# Mandala.net
KiCad netlist of a schematic drawn in EAGLE
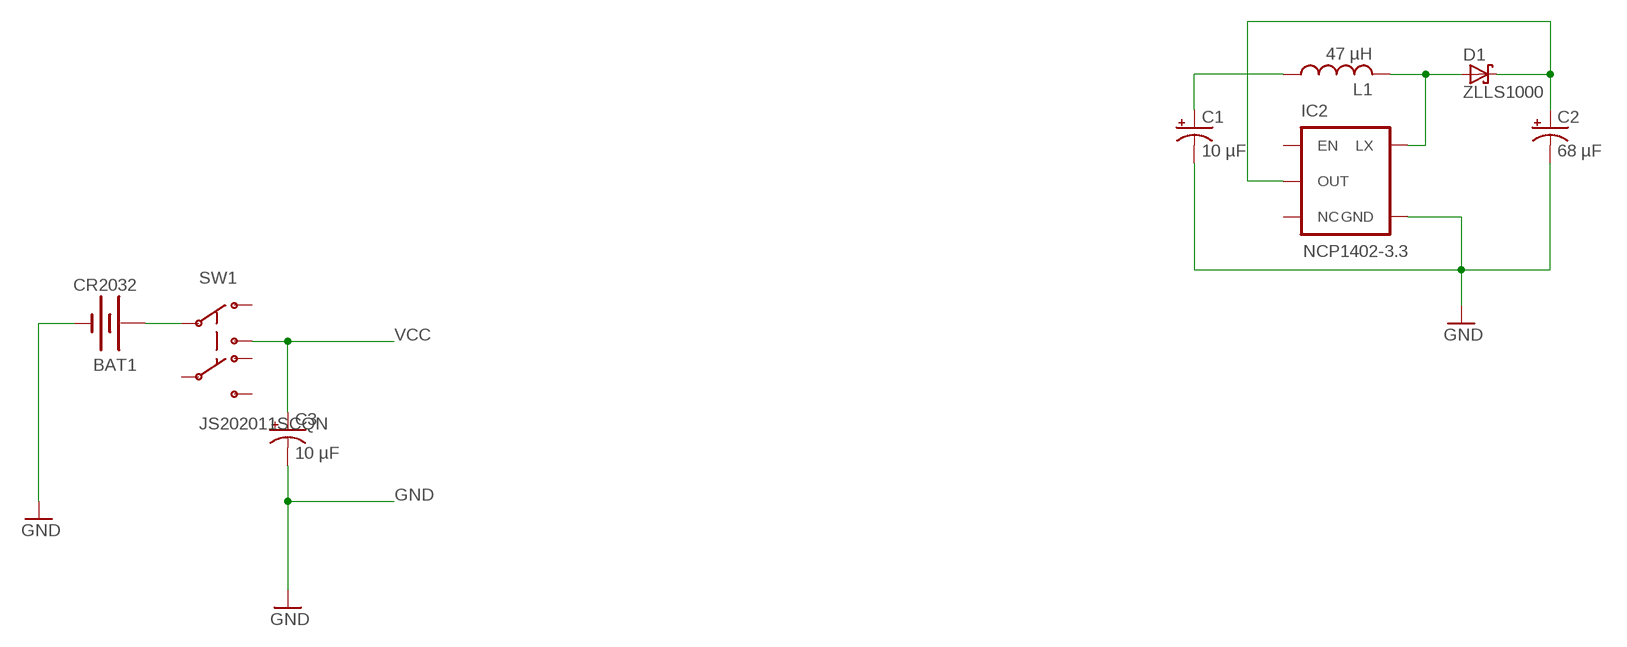
[diagram p0: schematic, sheet 1]

(export (version "E")
  (design (tool "Eeschema 10.0.6"))
  (components
    (comp (ref "BAT1")
      (value "CR2032")
      (footprint "eagle-import:BATTCON_20MM")
      (libsource (lib "eagle-import") (part "BATTERY20SMD-RIGHT"))
    )
    (comp (ref "C1")
      (value "10 µF")
      (footprint "eagle-import:SMC_B")
      (libsource (lib "eagle-import") (part "CPOL-USSMCB"))
    )
    (comp (ref "C2")
      (value "68 µF")
      (footprint "eagle-import:SMC_B")
      (libsource (lib "eagle-import") (part "CPOL-USSMCB"))
    )
    (comp (ref "C3")
      (value "10 µF")
      (footprint "eagle-import:SMC_B")
      (libsource (lib "eagle-import") (part "CPOL-USSMCB"))
    )
    (comp (ref "D1")
      (value "ZLLS1000")
      (footprint "eagle-import:SOT23")
      (libsource (lib "eagle-import") (part "BAS40"))
    )
    (comp (ref "IC2")
      (value "NCP1402-3.3")
      (footprint "eagle-import:SOT23-5")
      (libsource (lib "eagle-import") (part "V_REG_NCP1400SOT23-5"))
    )
    (comp (ref "L1")
      (value "47 µH")
      (footprint "eagle-import:ELL5PS_INDUCTOR")
      (libsource (lib "eagle-import") (part "PANASONIC_ELL5PS"))
    )
    (comp (ref "SW1")
      (value "JS202011SCQN")
      (footprint "eagle-import:JS202011SCQN_DPDT")
      (libsource (lib "eagle-import") (part "SW_DPDT_JS202011SCQN"))
    )
  )
  (nets
    (net (code "1") (name "/VCC") (class "Default")
      (node (ref "C1") (pin "+") (pinfunction "+_+") (pintype "passive"))
      (node (ref "C3") (pin "+") (pinfunction "+_+") (pintype "passive"))
      (node (ref "L1") (pin "P$1") (pinfunction "1_P$1") (pintype "passive"))
      (node (ref "SW1") (pin "P$3") (pinfunction "3_P$3") (pintype "bidirectional"))
    )
    (net (code "2") (name "GND") (class "Default")
      (node (ref "BAT1") (pin "2") (pinfunction "-_2") (pintype "power_in"))
      (node (ref "C1") (pin "-") (pinfunction "-_-") (pintype "passive"))
      (node (ref "C2") (pin "-") (pinfunction "-_-") (pintype "passive"))
      (node (ref "C3") (pin "-") (pinfunction "-_-") (pintype "passive"))
      (node (ref "IC2") (pin "4") (pinfunction "GND_4") (pintype "input"))
    )
    (net (code "3") (name "Net-(BAT1-+)") (class "Default")
      (node (ref "BAT1") (pin "3") (pinfunction "+_3") (pintype "power_in"))
      (node (ref "SW1") (pin "P$2") (pinfunction "2_P$2") (pintype "bidirectional"))
    )
    (net (code "4") (name "Net-(D1-A)") (class "Default")
      (node (ref "D1") (pin "1") (pinfunction "A_1") (pintype "passive"))
      (node (ref "IC2") (pin "5") (pinfunction "LX_5") (pintype "input"))
      (node (ref "L1") (pin "P$2") (pinfunction "2_P$2") (pintype "passive"))
    )
    (net (code "5") (name "Net-(D1-C)") (class "Default")
      (node (ref "C2") (pin "+") (pinfunction "+_+") (pintype "passive"))
      (node (ref "D1") (pin "3") (pinfunction "C_3") (pintype "passive"))
      (node (ref "IC2") (pin "2") (pinfunction "OUT_2") (pintype "passive"))
    )
    (net (code "6") (name "unconnected-(IC2-EN-Pad1)") (class "Default")
      (node (ref "IC2") (pin "1") (pinfunction "EN_1") (pintype "input"))
    )
    (net (code "7") (name "unconnected-(IC2-NC-Pad3)") (class "Default")
      (node (ref "IC2") (pin "3") (pinfunction "NC_3") (pintype "input"))
    )
    (net (code "8") (name "unconnected-(SW1-1-PadP$1)") (class "Default")
      (node (ref "SW1") (pin "P$1") (pinfunction "1_P$1") (pintype "bidirectional"))
    )
    (net (code "9") (name "unconnected-(SW1-4-PadP$4)") (class "Default")
      (node (ref "SW1") (pin "P$4") (pinfunction "4_P$4") (pintype "bidirectional"))
    )
    (net (code "10") (name "unconnected-(SW1-5-PadP$5)") (class "Default")
      (node (ref "SW1") (pin "P$5") (pinfunction "5_P$5") (pintype "bidirectional"))
    )
    (net (code "11") (name "unconnected-(SW1-6-PadP$6)") (class "Default")
      (node (ref "SW1") (pin "P$6") (pinfunction "6_P$6") (pintype "bidirectional"))
    )
  )
)
